# Gastroscopy-Tool-Interface_MCU.net
KiCad netlist of a schematic drawn in Altium Designer
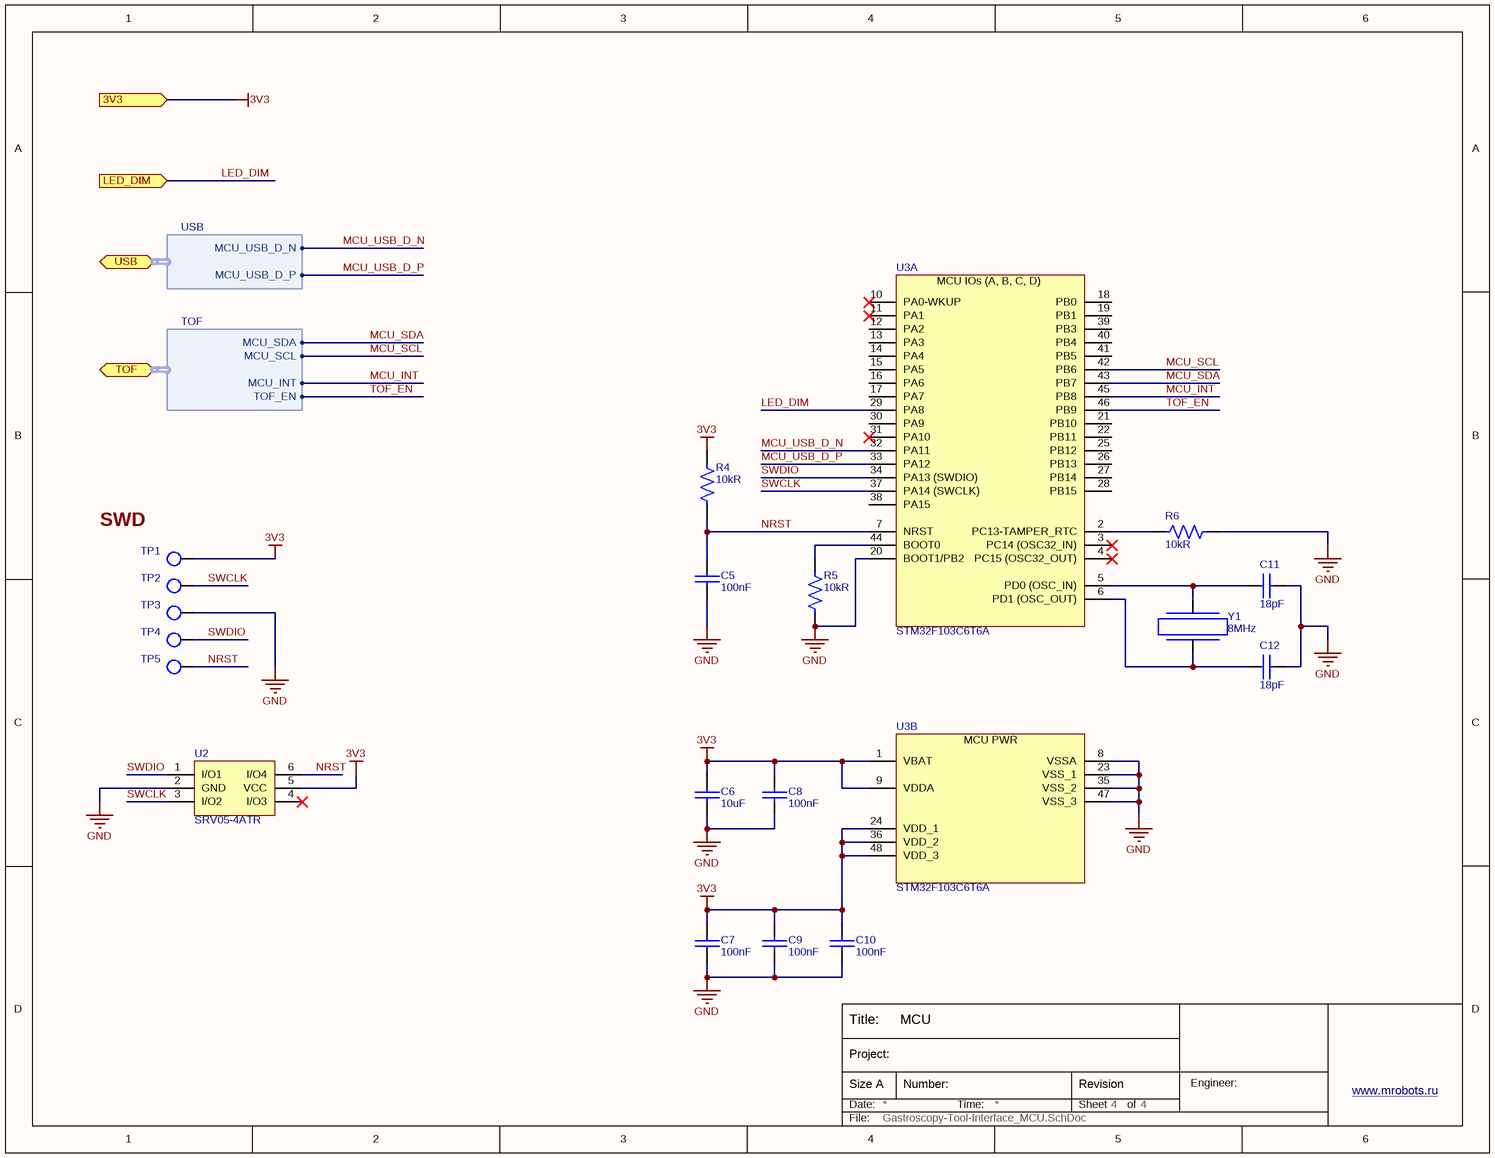
[diagram p0: Gastroscopy-Tool-Interface_MCU.SchDoc]

(export (version "E")
  (design (tool "Eeschema 10.0.6"))
  (components
    (comp (ref "C5")
      (value "100nF")
      (footprint "CAP_0603")
      (description "CAP CER 0.1UF 50V X7R 0603")
      (fields (field (name "TOLERANCE") "10%"))
      (libsource (lib "Industrial-Controller") (part "CL10B104KB8NNNL"))
    )
    (comp (ref "C6")
      (value "10uF")
      (footprint "CAP_0805")
      (description "CAP CER 10UF 16V X7R 0805")
      (fields
        (field (name "MANUFACTURER") "Samsung")
        (field (name "MANUFACTURER PART NUMBER") "CL21B106KOQNNNE")
      )
      (libsource (lib "Gastroscopy-Tool") (part "CL21B106KOQNNNE"))
    )
    (comp (ref "C7")
      (value "100nF")
      (footprint "CAP_0603")
      (description "CAP CER 0.1UF 50V X7R 0603")
      (fields (field (name "TOLERANCE") "10%"))
      (libsource (lib "Industrial-Controller") (part "CL10B104KB8NNNL"))
    )
    (comp (ref "C8")
      (value "100nF")
      (footprint "CAP_0603")
      (description "CAP CER 0.1UF 50V X7R 0603")
      (fields (field (name "TOLERANCE") "10%"))
      (libsource (lib "Industrial-Controller") (part "CL10B104KB8NNNL"))
    )
    (comp (ref "C9")
      (value "100nF")
      (footprint "CAP_0603")
      (description "CAP CER 0.1UF 50V X7R 0603")
      (fields (field (name "TOLERANCE") "10%"))
      (libsource (lib "Industrial-Controller") (part "CL10B104KB8NNNL"))
    )
    (comp (ref "C10")
      (value "100nF")
      (footprint "CAP_0603")
      (description "CAP CER 0.1UF 50V X7R 0603")
      (fields (field (name "TOLERANCE") "10%"))
      (libsource (lib "Industrial-Controller") (part "CL10B104KB8NNNL"))
    )
    (comp (ref "C11")
      (value "18pF")
      (footprint "CAP_0603")
      (description "CAP CER 18PF 50V C0G/NP0 0603")
      (fields
        (field (name "MANUFACTURER") "KEMET")
        (field (name "MANUFACTURER PART NUMBER") "C0603C180J5GACAUTO")
      )
      (libsource (lib "Industrial-Controller") (part "C0603C180J5GACAUTO"))
    )
    (comp (ref "C12")
      (value "18pF")
      (footprint "CAP_0603")
      (description "CAP CER 18PF 50V C0G/NP0 0603")
      (fields
        (field (name "MANUFACTURER") "KEMET")
        (field (name "MANUFACTURER PART NUMBER") "C0603C180J5GACAUTO")
      )
      (libsource (lib "Industrial-Controller") (part "C0603C180J5GACAUTO"))
    )
    (comp (ref "R4")
      (value "10kR")
      (footprint "RES_0603")
      (description "RES 10K OHM 1% 1/10W 0603")
      (fields (field (name "TOLERANCE") "1%"))
      (libsource (lib "Industrial-Controller") (part "RC0603FR-0710KL"))
    )
    (comp (ref "R5")
      (value "10kR")
      (footprint "RES_0603")
      (description "RES 10K OHM 1% 1/10W 0603")
      (fields (field (name "TOLERANCE") "1%"))
      (libsource (lib "Industrial-Controller") (part "RC0603FR-0710KL"))
    )
    (comp (ref "R6")
      (value "10kR")
      (footprint "RES_0603")
      (description "RES 10K OHM 1% 1/10W 0603")
      (fields (field (name "TOLERANCE") "1%"))
      (libsource (lib "Industrial-Controller") (part "RC0603FR-0710KL"))
    )
    (comp (ref "TP1")
      (value "TEST_POINT_SMT")
      (footprint "TEST_POINT_SMT")
      (description "STM TEST POINT")
      (libsource (lib "Gastroscopy-Tool") (part "TEST_POINT_SMT"))
    )
    (comp (ref "TP2")
      (value "TEST_POINT_SMT")
      (footprint "TEST_POINT_SMT")
      (description "STM TEST POINT")
      (libsource (lib "Gastroscopy-Tool") (part "TEST_POINT_SMT"))
    )
    (comp (ref "TP3")
      (value "TEST_POINT_SMT")
      (footprint "TEST_POINT_SMT")
      (description "STM TEST POINT")
      (libsource (lib "Gastroscopy-Tool") (part "TEST_POINT_SMT"))
    )
    (comp (ref "TP4")
      (value "TEST_POINT_SMT")
      (footprint "TEST_POINT_SMT")
      (description "STM TEST POINT")
      (libsource (lib "Gastroscopy-Tool") (part "TEST_POINT_SMT"))
    )
    (comp (ref "TP5")
      (value "TEST_POINT_SMT")
      (footprint "TEST_POINT_SMT")
      (description "STM TEST POINT")
      (libsource (lib "Gastroscopy-Tool") (part "TEST_POINT_SMT"))
    )
    (comp (ref "U2")
      (value "SRV05-4ATR")
      (footprint "SOT-23-6")
      (description "TVS DIODE 5VWM 17.5VC SOT23-6")
      (libsource (lib "Industrial-Controller") (part "SRV05-4ATR"))
    )
    (comp (ref "U3")
      (value "STM32F103C6T6A")
      (footprint "LQFP48")
      (description "IC MCU 32BIT 32KB FLASH 48LQFP")
      (libsource (lib "Industrial-Controller") (part "STM32F103C6T6A"))
    )
    (comp (ref "Y1")
      (value "8MHz")
      (footprint "HC-49/US")
      (description "CRYSTAL 8.0000MHZ 18PF TH")
      (fields (field (name "TOLERANCE") "30ppm"))
      (libsource (lib "Industrial-Controller") (part "ATS080B-E"))
    )
  )
  (nets
    (net (code "3") (name "/LED_DIM") (class "Default")
      (node (ref "U3") (pin "29") (pinfunction "PA8_29") (pintype "passive"))
    )
    (net (code "4") (name "/MCU_INT") (class "Default")
      (node (ref "U3") (pin "45") (pinfunction "PB8_45") (pintype "passive"))
    )
    (net (code "5") (name "/MCU_SCL") (class "Default")
      (node (ref "U3") (pin "42") (pinfunction "PB6_42") (pintype "passive"))
    )
    (net (code "6") (name "/MCU_SDA") (class "Default")
      (node (ref "U3") (pin "43") (pinfunction "PB7_43") (pintype "passive"))
    )
    (net (code "7") (name "/MCU_USB_D_N") (class "Default")
      (node (ref "U3") (pin "32") (pinfunction "PA11_32") (pintype "passive"))
    )
    (net (code "8") (name "/MCU_USB_D_P") (class "Default")
      (node (ref "U3") (pin "33") (pinfunction "PA12_33") (pintype "passive"))
    )
    (net (code "9") (name "/NRST") (class "Default")
      (node (ref "C5") (pin "1") (pinfunction "1_1") (pintype "passive"))
      (node (ref "R4") (pin "2") (pinfunction "2_2") (pintype "passive"))
      (node (ref "TP5") (pin "1") (pinfunction "1_1") (pintype "passive"))
      (node (ref "U2") (pin "6") (pinfunction "I/O4_6") (pintype "passive"))
      (node (ref "U3") (pin "7") (pinfunction "NRST_7") (pintype "passive"))
    )
    (net (code "10") (name "/SWCLK") (class "Default")
      (node (ref "TP2") (pin "1") (pinfunction "1_1") (pintype "passive"))
      (node (ref "U2") (pin "3") (pinfunction "I/O2_3") (pintype "passive"))
      (node (ref "U3") (pin "37") (pinfunction "PA14_(SWCLK)_37") (pintype "passive"))
    )
    (net (code "11") (name "/SWDIO") (class "Default")
      (node (ref "TP4") (pin "1") (pinfunction "1_1") (pintype "passive"))
      (node (ref "U2") (pin "1") (pinfunction "I/O1_1") (pintype "passive"))
      (node (ref "U3") (pin "34") (pinfunction "PA13_(SWDIO)_34") (pintype "passive"))
    )
    (net (code "12") (name "/TOF_EN") (class "Default")
      (node (ref "U3") (pin "46") (pinfunction "PB9_46") (pintype "passive"))
    )
    (net (code "15") (name "3V3") (class "Default")
      (node (ref "C10") (pin "1") (pinfunction "1_1") (pintype "passive"))
      (node (ref "C6") (pin "2") (pinfunction "2_2") (pintype "passive"))
      (node (ref "C7") (pin "1") (pinfunction "1_1") (pintype "passive"))
      (node (ref "C8") (pin "1") (pinfunction "1_1") (pintype "passive"))
      (node (ref "C9") (pin "1") (pinfunction "1_1") (pintype "passive"))
      (node (ref "R4") (pin "1") (pinfunction "1_1") (pintype "passive"))
      (node (ref "TP1") (pin "1") (pinfunction "1_1") (pintype "passive"))
      (node (ref "U2") (pin "5") (pinfunction "VCC_5") (pintype "passive"))
      (node (ref "U3") (pin "1") (pinfunction "VBAT_1") (pintype "passive"))
      (node (ref "U3") (pin "24") (pinfunction "VDD_1_24") (pintype "passive"))
      (node (ref "U3") (pin "36") (pinfunction "VDD_2_36") (pintype "passive"))
      (node (ref "U3") (pin "48") (pinfunction "VDD_3_48") (pintype "passive"))
      (node (ref "U3") (pin "9") (pinfunction "VDDA_9") (pintype "passive"))
    )
    (net (code "16") (name "GND") (class "Default")
      (node (ref "C10") (pin "2") (pinfunction "2_2") (pintype "passive"))
      (node (ref "C11") (pin "2") (pinfunction "2_2") (pintype "passive"))
      (node (ref "C12") (pin "2") (pinfunction "2_2") (pintype "passive"))
      (node (ref "C5") (pin "2") (pinfunction "2_2") (pintype "passive"))
      (node (ref "C6") (pin "1") (pinfunction "1_1") (pintype "passive"))
      (node (ref "C7") (pin "2") (pinfunction "2_2") (pintype "passive"))
      (node (ref "C8") (pin "2") (pinfunction "2_2") (pintype "passive"))
      (node (ref "C9") (pin "2") (pinfunction "2_2") (pintype "passive"))
      (node (ref "R5") (pin "1") (pinfunction "1_1") (pintype "passive"))
      (node (ref "R6") (pin "1") (pinfunction "1_1") (pintype "passive"))
      (node (ref "TP3") (pin "1") (pinfunction "1_1") (pintype "passive"))
      (node (ref "U2") (pin "2") (pinfunction "GND_2") (pintype "passive"))
      (node (ref "U3") (pin "20") (pinfunction "BOOT1/PB2_20") (pintype "passive"))
      (node (ref "U3") (pin "23") (pinfunction "VSS_1_23") (pintype "passive"))
      (node (ref "U3") (pin "35") (pinfunction "VSS_2_35") (pintype "passive"))
      (node (ref "U3") (pin "47") (pinfunction "VSS_3_47") (pintype "passive"))
      (node (ref "U3") (pin "8") (pinfunction "VSSA_8") (pintype "passive"))
    )
    (net (code "17") (name "Net-(U3A-BOOT0)") (class "Default")
      (node (ref "R5") (pin "2") (pinfunction "2_2") (pintype "passive"))
      (node (ref "U3") (pin "44") (pinfunction "BOOT0_44") (pintype "passive"))
    )
    (net (code "18") (name "Net-(U3A-PC13-TAMPER_RTC)") (class "Default")
      (node (ref "R6") (pin "2") (pinfunction "2_2") (pintype "passive"))
      (node (ref "U3") (pin "2") (pinfunction "PC13-TAMPER_RTC_2") (pintype "passive"))
    )
    (net (code "19") (name "Net-(U3A-PD0_(OSC_IN))") (class "Default")
      (node (ref "C11") (pin "1") (pinfunction "1_1") (pintype "passive"))
      (node (ref "U3") (pin "5") (pinfunction "PD0_(OSC_IN)_5") (pintype "passive"))
      (node (ref "Y1") (pin "2") (pinfunction "2_2") (pintype "passive"))
    )
    (net (code "20") (name "Net-(U3A-PD1_(OSC_OUT))") (class "Default")
      (node (ref "C12") (pin "1") (pinfunction "1_1") (pintype "passive"))
      (node (ref "U3") (pin "6") (pinfunction "PD1_(OSC_OUT)_6") (pintype "passive"))
      (node (ref "Y1") (pin "1") (pinfunction "1_1") (pintype "passive"))
    )
    (net (code "21") (name "unconnected-(U2-I{slash}O3-Pad4)") (class "Default")
      (node (ref "U2") (pin "4") (pinfunction "I/O3_4") (pintype "passive+no_connect"))
    )
    (net (code "22") (name "unconnected-(U3A-PA0-WKUP-Pad10)") (class "Default")
      (node (ref "U3") (pin "10") (pinfunction "PA0-WKUP_10") (pintype "passive+no_connect"))
    )
    (net (code "23") (name "unconnected-(U3A-PA1-Pad11)") (class "Default")
      (node (ref "U3") (pin "11") (pinfunction "PA1_11") (pintype "passive+no_connect"))
    )
    (net (code "24") (name "unconnected-(U3A-PA2-Pad12)") (class "Default")
      (node (ref "U3") (pin "12") (pinfunction "PA2_12") (pintype "passive"))
    )
    (net (code "25") (name "unconnected-(U3A-PA3-Pad13)") (class "Default")
      (node (ref "U3") (pin "13") (pinfunction "PA3_13") (pintype "passive"))
    )
    (net (code "26") (name "unconnected-(U3A-PA4-Pad14)") (class "Default")
      (node (ref "U3") (pin "14") (pinfunction "PA4_14") (pintype "passive"))
    )
    (net (code "27") (name "unconnected-(U3A-PA5-Pad15)") (class "Default")
      (node (ref "U3") (pin "15") (pinfunction "PA5_15") (pintype "passive"))
    )
    (net (code "28") (name "unconnected-(U3A-PA6-Pad16)") (class "Default")
      (node (ref "U3") (pin "16") (pinfunction "PA6_16") (pintype "passive"))
    )
    (net (code "29") (name "unconnected-(U3A-PA7-Pad17)") (class "Default")
      (node (ref "U3") (pin "17") (pinfunction "PA7_17") (pintype "passive"))
    )
    (net (code "30") (name "unconnected-(U3A-PA9-Pad30)") (class "Default")
      (node (ref "U3") (pin "30") (pinfunction "PA9_30") (pintype "passive"))
    )
    (net (code "31") (name "unconnected-(U3A-PA10-Pad31)") (class "Default")
      (node (ref "U3") (pin "31") (pinfunction "PA10_31") (pintype "passive+no_connect"))
    )
    (net (code "32") (name "unconnected-(U3A-PA15-Pad38)") (class "Default")
      (node (ref "U3") (pin "38") (pinfunction "PA15_38") (pintype "passive"))
    )
    (net (code "33") (name "unconnected-(U3A-PB0-Pad18)") (class "Default")
      (node (ref "U3") (pin "18") (pinfunction "PB0_18") (pintype "passive"))
    )
    (net (code "34") (name "unconnected-(U3A-PB1-Pad19)") (class "Default")
      (node (ref "U3") (pin "19") (pinfunction "PB1_19") (pintype "passive"))
    )
    (net (code "35") (name "unconnected-(U3A-PB3-Pad39)") (class "Default")
      (node (ref "U3") (pin "39") (pinfunction "PB3_39") (pintype "passive"))
    )
    (net (code "36") (name "unconnected-(U3A-PB4-Pad40)") (class "Default")
      (node (ref "U3") (pin "40") (pinfunction "PB4_40") (pintype "passive"))
    )
    (net (code "37") (name "unconnected-(U3A-PB5-Pad41)") (class "Default")
      (node (ref "U3") (pin "41") (pinfunction "PB5_41") (pintype "passive"))
    )
    (net (code "38") (name "unconnected-(U3A-PB10-Pad21)") (class "Default")
      (node (ref "U3") (pin "21") (pinfunction "PB10_21") (pintype "passive"))
    )
    (net (code "39") (name "unconnected-(U3A-PB11-Pad22)") (class "Default")
      (node (ref "U3") (pin "22") (pinfunction "PB11_22") (pintype "passive"))
    )
    (net (code "40") (name "unconnected-(U3A-PB12-Pad25)") (class "Default")
      (node (ref "U3") (pin "25") (pinfunction "PB12_25") (pintype "passive"))
    )
    (net (code "41") (name "unconnected-(U3A-PB13-Pad26)") (class "Default")
      (node (ref "U3") (pin "26") (pinfunction "PB13_26") (pintype "passive"))
    )
    (net (code "42") (name "unconnected-(U3A-PB14-Pad27)") (class "Default")
      (node (ref "U3") (pin "27") (pinfunction "PB14_27") (pintype "passive"))
    )
    (net (code "43") (name "unconnected-(U3A-PB15-Pad28)") (class "Default")
      (node (ref "U3") (pin "28") (pinfunction "PB15_28") (pintype "passive"))
    )
    (net (code "44") (name "unconnected-(U3A-PC14_(OSC32_IN)-Pad3)") (class "Default")
      (node (ref "U3") (pin "3") (pinfunction "PC14_(OSC32_IN)_3") (pintype "passive+no_connect"))
    )
    (net (code "45") (name "unconnected-(U3A-PC15_(OSC32_OUT)-Pad4)") (class "Default")
      (node (ref "U3") (pin "4") (pinfunction "PC15_(OSC32_OUT)_4") (pintype "passive+no_connect"))
    )
  )
)
